# DCDCFinalBoardLayout.net
KiCad netlist of a schematic drawn in EAGLE
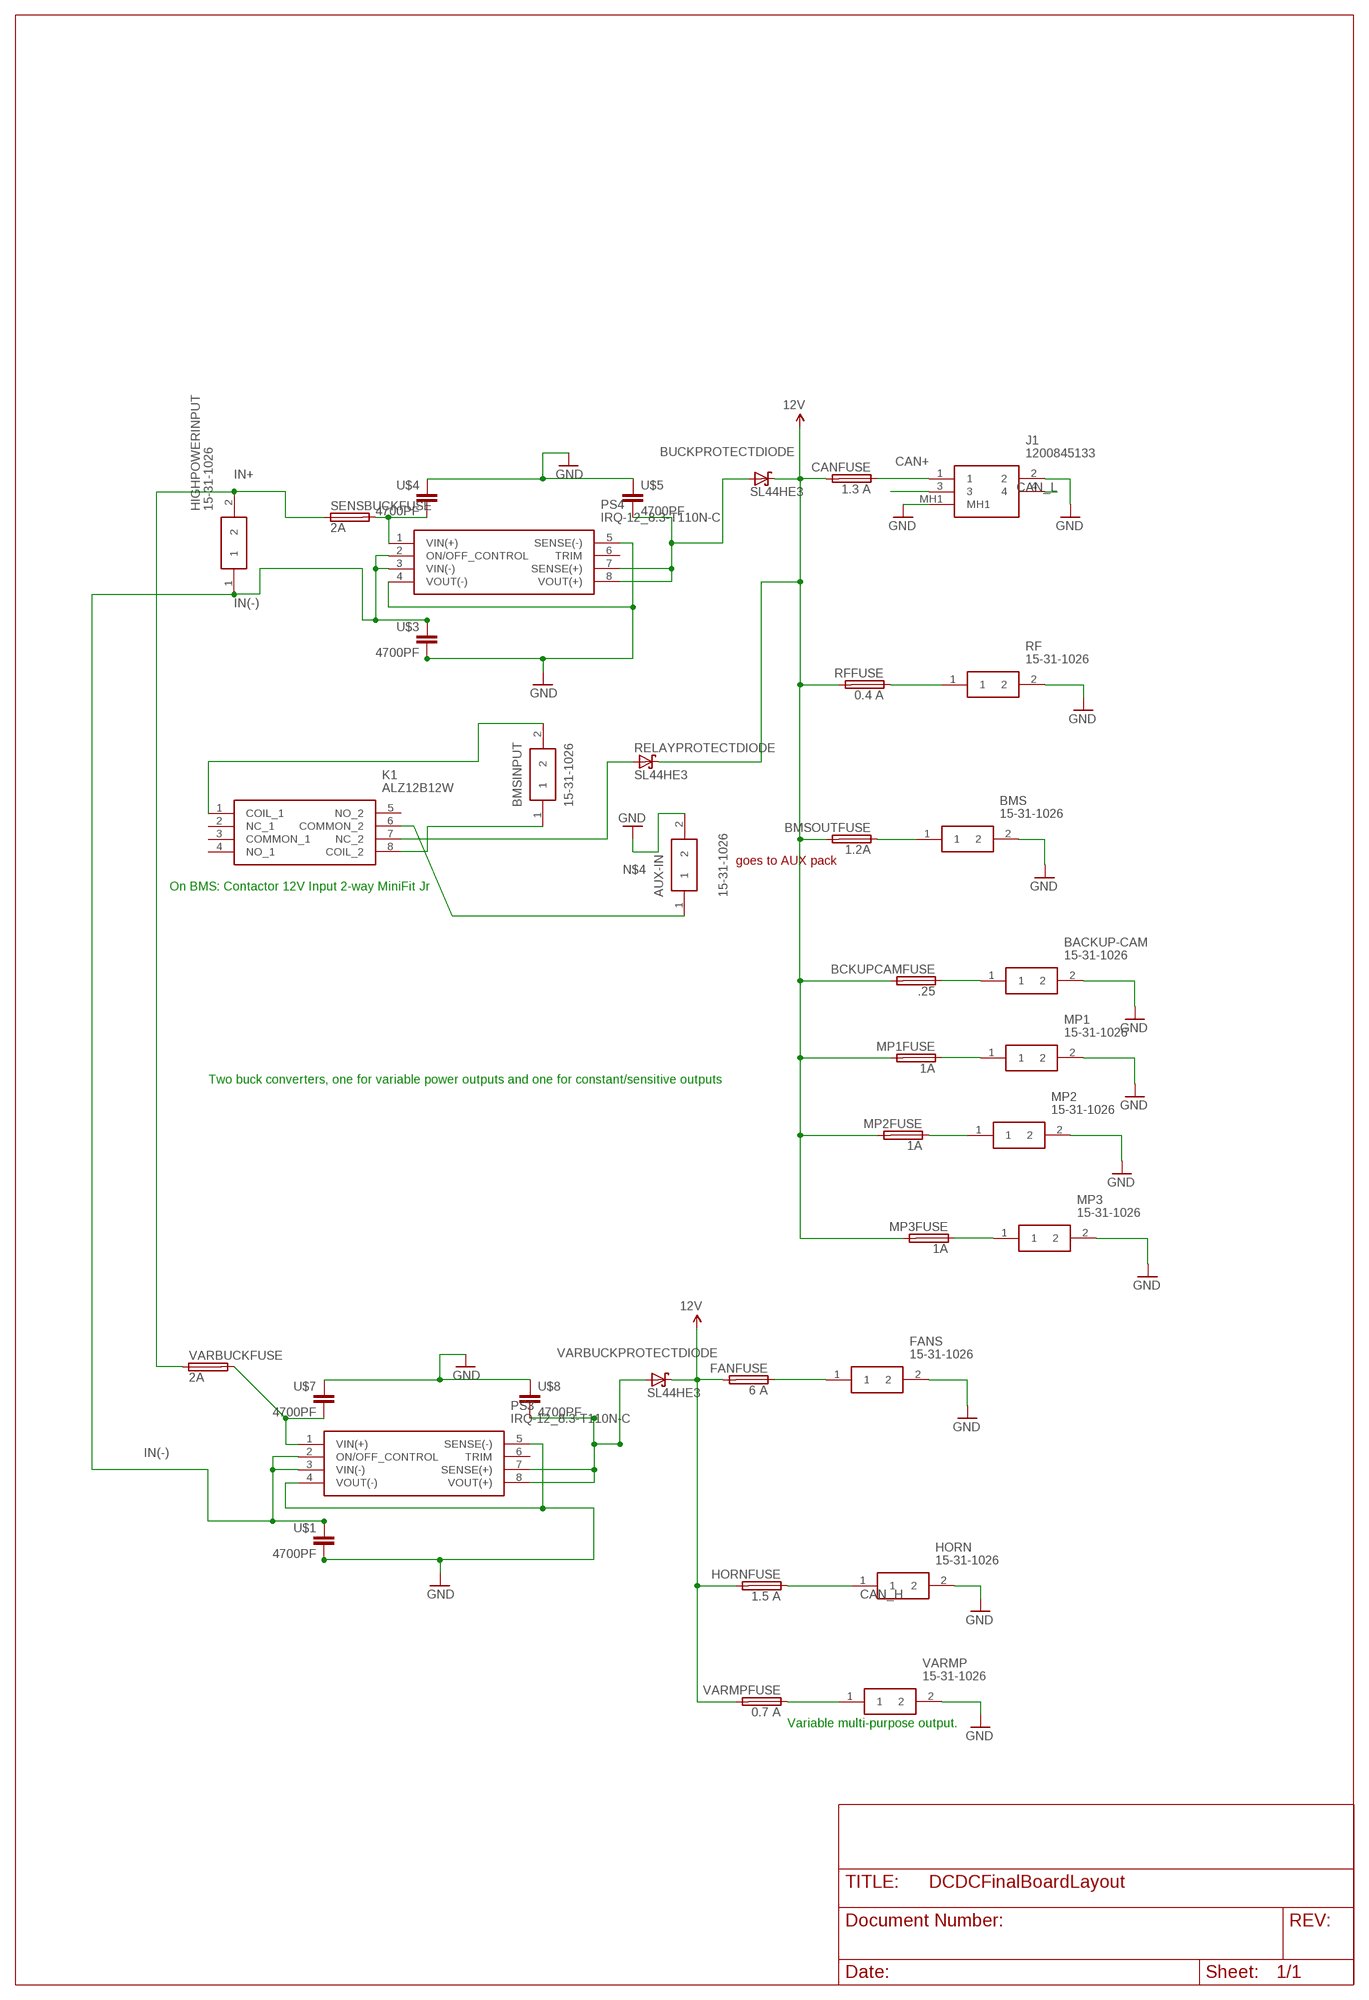
[diagram p0: schematic, sheet 1]

(export (version "E")
  (design (tool "Eeschema 10.0.6"))
  (components
    (comp (ref "AUX-IN")
      (value "15-31-1026")
      (footprint "eagle-import:15311026")
      (fields (field (name "MOUSER_PART_NUMBER") "538-15-31-1026"))
      (libsource (lib "eagle-import") (part "15-31-1026"))
    )
    (comp (ref "BACKUP-CAM")
      (value "15-31-1026")
      (footprint "eagle-import:15311026")
      (fields (field (name "MOUSER_PART_NUMBER") "538-15-31-1026"))
      (libsource (lib "eagle-import") (part "15-31-1026"))
    )
    (comp (ref "BCKUPCAMFUSE")
      (value ".25")
      (footprint "eagle-import:OMNIBLOK")
      (libsource (lib "eagle-import") (part "SMD-MICRO-FUSE-BLOCK"))
    )
    (comp (ref "BMS")
      (value "15-31-1026")
      (footprint "eagle-import:15311026")
      (fields (field (name "MOUSER_PART_NUMBER") "538-15-31-1026"))
      (libsource (lib "eagle-import") (part "15-31-1026"))
    )
    (comp (ref "BMSINPUT")
      (value "15-31-1026")
      (footprint "eagle-import:15311026")
      (fields (field (name "MOUSER_PART_NUMBER") "538-15-31-1026"))
      (libsource (lib "eagle-import") (part "15-31-1026"))
    )
    (comp (ref "BMSOUTFUSE")
      (value "1.2A")
      (footprint "eagle-import:OMNIBLOK")
      (libsource (lib "eagle-import") (part "SMD-MICRO-FUSE-BLOCK"))
    )
    (comp (ref "BUCKPROTECTDIODE")
      (value "SL44HE3")
      (footprint "eagle-import:SMC")
      (libsource (lib "eagle-import") (part "SL44HE3"))
    )
    (comp (ref "CANFUSE")
      (value "1.3 A")
      (footprint "eagle-import:OMNIBLOK")
      (libsource (lib "eagle-import") (part "SMD-MICRO-FUSE-BLOCK"))
    )
    (comp (ref "FANFUSE")
      (value "6 A")
      (footprint "eagle-import:OMNIBLOK")
      (libsource (lib "eagle-import") (part "SMD-MICRO-FUSE-BLOCK"))
    )
    (comp (ref "FANS")
      (value "15-31-1026")
      (footprint "eagle-import:15311026")
      (fields (field (name "MOUSER_PART_NUMBER") "538-15-31-1026"))
      (libsource (lib "eagle-import") (part "15-31-1026"))
    )
    (comp (ref "HIGHPOWERINPUT")
      (value "15-31-1026")
      (footprint "eagle-import:15311026")
      (fields (field (name "MOUSER_PART_NUMBER") "538-15-31-1026"))
      (libsource (lib "eagle-import") (part "15-31-1026"))
    )
    (comp (ref "HORN")
      (value "15-31-1026")
      (footprint "eagle-import:15311026")
      (fields (field (name "MOUSER_PART_NUMBER") "538-15-31-1026"))
      (libsource (lib "eagle-import") (part "15-31-1026"))
    )
    (comp (ref "HORNFUSE")
      (value "1.5 A")
      (footprint "eagle-import:OMNIBLOK")
      (libsource (lib "eagle-import") (part "SMD-MICRO-FUSE-BLOCK"))
    )
    (comp (ref "J1")
      (value "1200845133")
      (footprint "eagle-import:1200845133")
      (fields (field (name "MOUSER_PART_NUMBER") "538-1200845133"))
      (libsource (lib "eagle-import") (part "1200845133"))
    )
    (comp (ref "K1")
      (value "ALZ12B12W")
      (footprint "eagle-import:ALZ12B12W")
      (libsource (lib "eagle-import") (part "ALZ12B12W"))
    )
    (comp (ref "MP1")
      (value "15-31-1026")
      (footprint "eagle-import:15311026")
      (fields (field (name "MOUSER_PART_NUMBER") "538-15-31-1026"))
      (libsource (lib "eagle-import") (part "15-31-1026"))
    )
    (comp (ref "MP1FUSE")
      (value "1A")
      (footprint "eagle-import:OMNIBLOK")
      (libsource (lib "eagle-import") (part "SMD-MICRO-FUSE-BLOCK"))
    )
    (comp (ref "MP2")
      (value "15-31-1026")
      (footprint "eagle-import:15311026")
      (fields (field (name "MOUSER_PART_NUMBER") "538-15-31-1026"))
      (libsource (lib "eagle-import") (part "15-31-1026"))
    )
    (comp (ref "MP2FUSE")
      (value "1A")
      (footprint "eagle-import:OMNIBLOK")
      (libsource (lib "eagle-import") (part "SMD-MICRO-FUSE-BLOCK"))
    )
    (comp (ref "MP3")
      (value "15-31-1026")
      (footprint "eagle-import:15311026")
      (fields (field (name "MOUSER_PART_NUMBER") "538-15-31-1026"))
      (libsource (lib "eagle-import") (part "15-31-1026"))
    )
    (comp (ref "MP3FUSE")
      (value "1A")
      (footprint "eagle-import:OMNIBLOK")
      (libsource (lib "eagle-import") (part "SMD-MICRO-FUSE-BLOCK"))
    )
    (comp (ref "PS3")
      (value "IRQ-12_8.3-T110N-C")
      (footprint "eagle-import:IRQ1283T110NC")
      (fields
        (field (name "MANUFACTURER_PART_NUMBER") "IRQ-12/8.3-T110N-C")
        (field (name "MOUSER_PART_NUMBER") "580-IRQ-12/8.3T110NC")
      )
      (libsource (lib "eagle-import") (part "IRQ-12_8.3-T110N-C"))
    )
    (comp (ref "PS4")
      (value "IRQ-12_8.3-T110N-C")
      (footprint "eagle-import:IRQ1283T110NC")
      (fields
        (field (name "MANUFACTURER_PART_NUMBER") "IRQ-12/8.3-T110N-C")
        (field (name "MOUSER_PART_NUMBER") "580-IRQ-12/8.3T110NC")
      )
      (libsource (lib "eagle-import") (part "IRQ-12_8.3-T110N-C"))
    )
    (comp (ref "RELAYPROTECTDIODE")
      (value "SL44HE3")
      (footprint "eagle-import:SMC")
      (libsource (lib "eagle-import") (part "SL44HE3"))
    )
    (comp (ref "RF")
      (value "15-31-1026")
      (footprint "eagle-import:15311026")
      (fields (field (name "MOUSER_PART_NUMBER") "538-15-31-1026"))
      (libsource (lib "eagle-import") (part "15-31-1026"))
    )
    (comp (ref "RFFUSE")
      (value "0.4 A")
      (footprint "eagle-import:OMNIBLOK")
      (libsource (lib "eagle-import") (part "SMD-MICRO-FUSE-BLOCK"))
    )
    (comp (ref "SENSBUCKFUSE")
      (value "2A")
      (footprint "eagle-import:OMNIBLOK")
      (libsource (lib "eagle-import") (part "SMD-MICRO-FUSE-BLOCK"))
    )
    (comp (ref "U$1")
      (value "4700PF")
      (footprint "eagle-import:Y2_CAP")
      (libsource (lib "eagle-import") (part "4700PF"))
    )
    (comp (ref "U$3")
      (value "4700PF")
      (footprint "eagle-import:Y2_CAP")
      (libsource (lib "eagle-import") (part "4700PF"))
    )
    (comp (ref "U$4")
      (value "4700PF")
      (footprint "eagle-import:Y2_CAP")
      (libsource (lib "eagle-import") (part "4700PF"))
    )
    (comp (ref "U$5")
      (value "4700PF")
      (footprint "eagle-import:Y2_CAP")
      (libsource (lib "eagle-import") (part "4700PF"))
    )
    (comp (ref "U$7")
      (value "4700PF")
      (footprint "eagle-import:Y2_CAP")
      (libsource (lib "eagle-import") (part "4700PF"))
    )
    (comp (ref "U$8")
      (value "4700PF")
      (footprint "eagle-import:Y2_CAP")
      (libsource (lib "eagle-import") (part "4700PF"))
    )
    (comp (ref "VARBUCKFUSE")
      (value "2A")
      (footprint "eagle-import:OMNIBLOK")
      (libsource (lib "eagle-import") (part "SMD-MICRO-FUSE-BLOCK"))
    )
    (comp (ref "VARBUCKPROTECTDIODE")
      (value "SL44HE3")
      (footprint "eagle-import:SMC")
      (libsource (lib "eagle-import") (part "SL44HE3"))
    )
    (comp (ref "VARMP")
      (value "15-31-1026")
      (footprint "eagle-import:15311026")
      (fields (field (name "MOUSER_PART_NUMBER") "538-15-31-1026"))
      (libsource (lib "eagle-import") (part "15-31-1026"))
    )
    (comp (ref "VARMPFUSE")
      (value "0.7 A")
      (footprint "eagle-import:OMNIBLOK")
      (libsource (lib "eagle-import") (part "SMD-MICRO-FUSE-BLOCK"))
    )
  )
  (nets
    (net (code "1") (name "/CAN+") (class "Default")
      (node (ref "BACKUP-CAM") (pin "1") (pinfunction "1_1") (pintype "bidirectional"))
      (node (ref "BCKUPCAMFUSE") (pin "P$1") (pinfunction "1_P$1") (pintype "passive"))
      (node (ref "CANFUSE") (pin "P$1") (pinfunction "1_P$1") (pintype "passive"))
      (node (ref "J1") (pin "1") (pinfunction "1_1") (pintype "bidirectional"))
    )
    (net (code "2") (name "/CAN_H") (class "Default")
      (node (ref "J1") (pin "3") (pinfunction "3_3") (pintype "bidirectional"))
    )
    (net (code "3") (name "/CAN_L") (class "Default")
      (node (ref "J1") (pin "4") (pinfunction "4_4") (pintype "bidirectional"))
    )
    (net (code "4") (name "/IN(-)") (class "Default")
      (node (ref "HIGHPOWERINPUT") (pin "1") (pinfunction "1_1") (pintype "bidirectional"))
      (node (ref "PS3") (pin "2") (pinfunction "ON/OFF_CONTROL_2") (pintype "bidirectional"))
      (node (ref "PS3") (pin "3") (pinfunction "VIN(-)_3") (pintype "bidirectional"))
      (node (ref "PS4") (pin "2") (pinfunction "ON/OFF_CONTROL_2") (pintype "bidirectional"))
      (node (ref "PS4") (pin "3") (pinfunction "VIN(-)_3") (pintype "bidirectional"))
      (node (ref "U$1") (pin "P$1") (pinfunction "1_P$1") (pintype "passive"))
      (node (ref "U$3") (pin "P$1") (pinfunction "1_P$1") (pintype "passive"))
    )
    (net (code "5") (name "/IN+") (class "Default")
      (node (ref "HIGHPOWERINPUT") (pin "2") (pinfunction "2_2") (pintype "bidirectional"))
      (node (ref "SENSBUCKFUSE") (pin "P$1") (pinfunction "1_P$1") (pintype "passive"))
      (node (ref "VARBUCKFUSE") (pin "P$1") (pinfunction "1_P$1") (pintype "passive"))
    )
    (net (code "6") (name "/N$4") (class "Default")
      (node (ref "BMSINPUT") (pin "2") (pinfunction "2_2") (pintype "bidirectional"))
      (node (ref "K1") (pin "1") (pinfunction "COIL_1_1") (pintype "bidirectional"))
      (node (ref "K1") (pin "7") (pinfunction "NC_2_7") (pintype "bidirectional"))
      (node (ref "RELAYPROTECTDIODE") (pin "A") (pinfunction "A_A") (pintype "passive"))
    )
    (net (code "7") (name "12V") (class "Default")
      (node (ref "BCKUPCAMFUSE") (pin "P$2") (pinfunction "2_P$2") (pintype "passive"))
      (node (ref "BMSOUTFUSE") (pin "P$2") (pinfunction "2_P$2") (pintype "passive"))
      (node (ref "BUCKPROTECTDIODE") (pin "C") (pinfunction "C_C") (pintype "passive"))
      (node (ref "CANFUSE") (pin "P$2") (pinfunction "2_P$2") (pintype "passive"))
      (node (ref "FANFUSE") (pin "P$2") (pinfunction "2_P$2") (pintype "passive"))
      (node (ref "HORNFUSE") (pin "P$2") (pinfunction "2_P$2") (pintype "passive"))
      (node (ref "MP1FUSE") (pin "P$2") (pinfunction "2_P$2") (pintype "passive"))
      (node (ref "MP2FUSE") (pin "P$2") (pinfunction "2_P$2") (pintype "passive"))
      (node (ref "MP3FUSE") (pin "P$2") (pinfunction "2_P$2") (pintype "passive"))
      (node (ref "RELAYPROTECTDIODE") (pin "C") (pinfunction "C_C") (pintype "passive"))
      (node (ref "RFFUSE") (pin "P$2") (pinfunction "2_P$2") (pintype "passive"))
      (node (ref "VARBUCKPROTECTDIODE") (pin "C") (pinfunction "C_C") (pintype "passive"))
      (node (ref "VARMPFUSE") (pin "P$2") (pinfunction "2_P$2") (pintype "passive"))
    )
    (net (code "8") (name "GND") (class "Default")
      (node (ref "AUX-IN") (pin "2") (pinfunction "2_2") (pintype "bidirectional"))
      (node (ref "BACKUP-CAM") (pin "2") (pinfunction "2_2") (pintype "bidirectional"))
      (node (ref "BMS") (pin "2") (pinfunction "2_2") (pintype "bidirectional"))
      (node (ref "FANS") (pin "2") (pinfunction "2_2") (pintype "bidirectional"))
      (node (ref "HORN") (pin "2") (pinfunction "2_2") (pintype "bidirectional"))
      (node (ref "J1") (pin "2") (pinfunction "2_2") (pintype "bidirectional"))
      (node (ref "J1") (pin "MH1") (pinfunction "MH1_MH1") (pintype "bidirectional"))
      (node (ref "MP1") (pin "2") (pinfunction "2_2") (pintype "bidirectional"))
      (node (ref "MP2") (pin "2") (pinfunction "2_2") (pintype "bidirectional"))
      (node (ref "MP3") (pin "2") (pinfunction "2_2") (pintype "bidirectional"))
      (node (ref "PS3") (pin "4") (pinfunction "VOUT(-)_4") (pintype "bidirectional"))
      (node (ref "PS3") (pin "5") (pinfunction "SENSE(-)_5") (pintype "bidirectional"))
      (node (ref "PS4") (pin "4") (pinfunction "VOUT(-)_4") (pintype "bidirectional"))
      (node (ref "PS4") (pin "5") (pinfunction "SENSE(-)_5") (pintype "bidirectional"))
      (node (ref "RF") (pin "2") (pinfunction "2_2") (pintype "bidirectional"))
      (node (ref "U$1") (pin "P$2") (pinfunction "2_P$2") (pintype "passive"))
      (node (ref "U$3") (pin "P$2") (pinfunction "2_P$2") (pintype "passive"))
      (node (ref "U$4") (pin "P$1") (pinfunction "1_P$1") (pintype "passive"))
      (node (ref "U$5") (pin "P$1") (pinfunction "1_P$1") (pintype "passive"))
      (node (ref "U$7") (pin "P$1") (pinfunction "1_P$1") (pintype "passive"))
      (node (ref "U$8") (pin "P$1") (pinfunction "1_P$1") (pintype "passive"))
      (node (ref "VARMP") (pin "2") (pinfunction "2_2") (pintype "bidirectional"))
    )
    (net (code "9") (name "Net-(BMSOUTFUSE-1)") (class "Default")
      (node (ref "BMS") (pin "1") (pinfunction "1_1") (pintype "bidirectional"))
      (node (ref "BMSOUTFUSE") (pin "P$1") (pinfunction "1_P$1") (pintype "passive"))
    )
    (net (code "10") (name "Net-(FANFUSE-1)") (class "Default")
      (node (ref "FANFUSE") (pin "P$1") (pinfunction "1_P$1") (pintype "passive"))
      (node (ref "FANS") (pin "1") (pinfunction "1_1") (pintype "bidirectional"))
    )
    (net (code "11") (name "Net-(HORNFUSE-1)") (class "Default")
      (node (ref "HORN") (pin "1") (pinfunction "1_1") (pintype "bidirectional"))
      (node (ref "HORNFUSE") (pin "P$1") (pinfunction "1_P$1") (pintype "passive"))
    )
    (net (code "12") (name "Net-(K1-COIL_2)") (class "Default")
      (node (ref "BMSINPUT") (pin "1") (pinfunction "1_1") (pintype "bidirectional"))
      (node (ref "K1") (pin "8") (pinfunction "COIL_2_8") (pintype "bidirectional"))
    )
    (net (code "13") (name "Net-(K1-COMMON_2)") (class "Default")
      (node (ref "AUX-IN") (pin "1") (pinfunction "1_1") (pintype "bidirectional"))
      (node (ref "K1") (pin "6") (pinfunction "COMMON_2_6") (pintype "bidirectional"))
    )
    (net (code "14") (name "Net-(MP1FUSE-1)") (class "Default")
      (node (ref "MP1") (pin "1") (pinfunction "1_1") (pintype "bidirectional"))
      (node (ref "MP1FUSE") (pin "P$1") (pinfunction "1_P$1") (pintype "passive"))
    )
    (net (code "15") (name "Net-(MP2FUSE-1)") (class "Default")
      (node (ref "MP2") (pin "1") (pinfunction "1_1") (pintype "bidirectional"))
      (node (ref "MP2FUSE") (pin "P$1") (pinfunction "1_P$1") (pintype "passive"))
    )
    (net (code "16") (name "Net-(MP3FUSE-1)") (class "Default")
      (node (ref "MP3") (pin "1") (pinfunction "1_1") (pintype "bidirectional"))
      (node (ref "MP3FUSE") (pin "P$1") (pinfunction "1_P$1") (pintype "passive"))
    )
    (net (code "17") (name "Net-(PS3-SENSE(+))") (class "Default")
      (node (ref "PS3") (pin "7") (pinfunction "SENSE(+)_7") (pintype "bidirectional"))
      (node (ref "PS3") (pin "8") (pinfunction "VOUT(+)_8") (pintype "bidirectional"))
      (node (ref "U$8") (pin "P$2") (pinfunction "2_P$2") (pintype "passive"))
      (node (ref "VARBUCKPROTECTDIODE") (pin "A") (pinfunction "A_A") (pintype "passive"))
    )
    (net (code "18") (name "Net-(PS3-VIN(+))") (class "Default")
      (node (ref "PS3") (pin "1") (pinfunction "VIN(+)_1") (pintype "bidirectional"))
      (node (ref "U$7") (pin "P$2") (pinfunction "2_P$2") (pintype "passive"))
      (node (ref "VARBUCKFUSE") (pin "P$2") (pinfunction "2_P$2") (pintype "passive"))
    )
    (net (code "19") (name "Net-(PS4-SENSE(+))") (class "Default")
      (node (ref "BUCKPROTECTDIODE") (pin "A") (pinfunction "A_A") (pintype "passive"))
      (node (ref "PS4") (pin "7") (pinfunction "SENSE(+)_7") (pintype "bidirectional"))
      (node (ref "PS4") (pin "8") (pinfunction "VOUT(+)_8") (pintype "bidirectional"))
      (node (ref "U$5") (pin "P$2") (pinfunction "2_P$2") (pintype "passive"))
    )
    (net (code "20") (name "Net-(PS4-VIN(+))") (class "Default")
      (node (ref "PS4") (pin "1") (pinfunction "VIN(+)_1") (pintype "bidirectional"))
      (node (ref "SENSBUCKFUSE") (pin "P$2") (pinfunction "2_P$2") (pintype "passive"))
      (node (ref "U$4") (pin "P$2") (pinfunction "2_P$2") (pintype "passive"))
    )
    (net (code "21") (name "Net-(RFFUSE-1)") (class "Default")
      (node (ref "RF") (pin "1") (pinfunction "1_1") (pintype "bidirectional"))
      (node (ref "RFFUSE") (pin "P$1") (pinfunction "1_P$1") (pintype "passive"))
    )
    (net (code "22") (name "Net-(VARMPFUSE-1)") (class "Default")
      (node (ref "VARMP") (pin "1") (pinfunction "1_1") (pintype "bidirectional"))
      (node (ref "VARMPFUSE") (pin "P$1") (pinfunction "1_P$1") (pintype "passive"))
    )
    (net (code "23") (name "unconnected-(K1-COMMON_1-Pad3)") (class "Default")
      (node (ref "K1") (pin "3") (pinfunction "COMMON_1_3") (pintype "bidirectional"))
    )
    (net (code "24") (name "unconnected-(K1-NC_1-Pad2)") (class "Default")
      (node (ref "K1") (pin "2") (pinfunction "NC_1_2") (pintype "bidirectional"))
    )
    (net (code "25") (name "unconnected-(K1-NO_1-Pad4)") (class "Default")
      (node (ref "K1") (pin "4") (pinfunction "NO_1_4") (pintype "bidirectional"))
    )
    (net (code "26") (name "unconnected-(K1-NO_2-Pad5)") (class "Default")
      (node (ref "K1") (pin "5") (pinfunction "NO_2_5") (pintype "bidirectional"))
    )
    (net (code "27") (name "unconnected-(PS3-TRIM-Pad6)") (class "Default")
      (node (ref "PS3") (pin "6") (pinfunction "TRIM_6") (pintype "bidirectional"))
    )
    (net (code "28") (name "unconnected-(PS4-TRIM-Pad6)") (class "Default")
      (node (ref "PS4") (pin "6") (pinfunction "TRIM_6") (pintype "bidirectional"))
    )
  )
)
